# phase_reference.net
KiCad netlist of a schematic drawn in Altium Designer
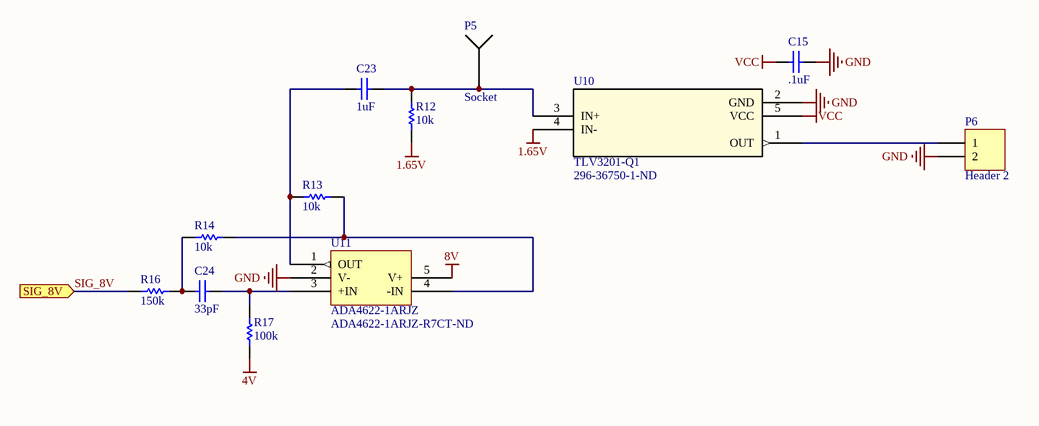
[diagram p0: phase_reference.SchDoc]

(export (version "E")
  (design (tool "Eeschema 10.0.6"))
  (components
    (comp (ref "C15")
      (value ".1uF")
      (footprint "0603")
      (description "Ceramic Capacitor (Surface Mount)")
      (fields (field (name "MANUFACTURER") "Generic Ceramic Chip Cap (TBD)") (field (name "Comment") "Cap"))
      (libsource (lib "maglib") (part "Cap"))
    )
    (comp (ref "C23")
      (value "1uF")
      (footprint "0603")
      (description "Ceramic Capacitor (Surface Mount)")
      (fields (field (name "MANUFACTURER") "Generic Ceramic Chip Cap (TBD)") (field (name "Comment") "Cap"))
      (libsource (lib "maglib") (part "Cap"))
    )
    (comp (ref "C24")
      (value "33pF")
      (footprint "0603")
      (description "Ceramic Capacitor (Surface Mount)")
      (fields (field (name "MANUFACTURER") "Generic Ceramic Chip Cap (TBD)") (field (name "Comment") "Cap"))
      (libsource (lib "maglib") (part "Cap"))
    )
    (comp (ref "P5") (value "Socket") (footprint "socket") (libsource (lib "maglib") (part "Socket")))
    (comp (ref "P6")
      (value "Header 2")
      (footprint "HDR1X2")
      (description "Header, 2-Pin")
      (fields (field (name "PUBLISHER") "Altium Limited"))
      (libsource (lib "Miscellaneous Connectors") (part "Header 2"))
    )
    (comp (ref "R12")
      (value "10k")
      (footprint "0603")
      (description "Chip Resistor (Surface Mount)")
      (fields (field (name "MANUFACTURER") "Generic Chip Res (TBD)") (field (name "Comment") "Res"))
      (libsource (lib "maglib") (part "Res"))
    )
    (comp (ref "R13")
      (value "10k")
      (footprint "0603")
      (description "Chip Resistor (Surface Mount)")
      (fields (field (name "MANUFACTURER") "Generic Chip Res (TBD)") (field (name "Comment") "Res"))
      (libsource (lib "maglib") (part "Res"))
    )
    (comp (ref "R14")
      (value "10k")
      (footprint "0603")
      (description "Chip Resistor (Surface Mount)")
      (fields (field (name "MANUFACTURER") "Generic Chip Res (TBD)") (field (name "Comment") "Res"))
      (libsource (lib "maglib") (part "Res"))
    )
    (comp (ref "R16")
      (value "150k")
      (footprint "0603")
      (description "Chip Resistor (Surface Mount)")
      (fields (field (name "MANUFACTURER") "Generic Chip Res (TBD)") (field (name "Comment") "Res"))
      (libsource (lib "maglib") (part "Res"))
    )
    (comp (ref "R17")
      (value "100k")
      (footprint "0603")
      (description "Chip Resistor (Surface Mount)")
      (fields (field (name "MANUFACTURER") "Generic Chip Res (TBD)") (field (name "Comment") "Res"))
      (libsource (lib "maglib") (part "Res"))
    )
    (comp (ref "U10")
      (value "TLV3201-Q1")
      (footprint "SOT95P280X145-5N")
      (description "40-ns, Micropower Comparator")
      (fields (field (name "SUPPLIER PART NUMBER 1") "296-36750-1-ND"))
      (libsource (lib "maglib") (part "TLV3201-Q1"))
    )
    (comp (ref "U11")
      (value "ADA4622-1ARJZ")
      (footprint "SOT95P280X145-5N")
      (description "30 V, 8 MHz, Low Bias Current,\r\nSingle-Supply, RRO, Precision Op Amps")
      (fields (field (name "SUPPLIER PART NUMBER 1") "ADA4622-1ARJZ-R7CT-ND"))
      (libsource (lib "maglib") (part "ADA4622-1ARJZ"))
    )
  )
  (nets
    (net (code "1") (name "/SIG_8V") (class "Default")
      (node (ref "R16") (pin "2") (pinfunction "2_2") (pintype "passive"))
    )
    (net (code "2") (name "1.65V") (class "Default")
      (node (ref "R12") (pin "1") (pinfunction "1_1") (pintype "passive"))
      (node (ref "U10") (pin "4") (pinfunction "IN-_4") (pintype "passive"))
    )
    (net (code "3") (name "4V") (class "Default")
      (node (ref "R17") (pin "1") (pinfunction "1_1") (pintype "passive"))
    )
    (net (code "4") (name "8V") (class "Default")
      (node (ref "U11") (pin "5") (pinfunction "V+_5") (pintype "power_in"))
    )
    (net (code "5") (name "GND") (class "Default")
      (node (ref "C15") (pin "2") (pinfunction "2_2") (pintype "passive"))
      (node (ref "P6") (pin "2") (pinfunction "2_2") (pintype "passive"))
      (node (ref "U10") (pin "2") (pinfunction "GND_2") (pintype "power_in"))
      (node (ref "U11") (pin "2") (pinfunction "V-_2") (pintype "power_in"))
    )
    (net (code "6") (name "Net-(C24-Pad2)") (class "Default")
      (node (ref "C24") (pin "2") (pinfunction "2_2") (pintype "passive"))
      (node (ref "R14") (pin "2") (pinfunction "2_2") (pintype "passive"))
      (node (ref "R16") (pin "1") (pinfunction "1_1") (pintype "passive"))
    )
    (net (code "7") (name "Net-(U10-IN+)") (class "Default")
      (node (ref "C23") (pin "1") (pinfunction "1_1") (pintype "passive"))
      (node (ref "P5") (pin "0") (pinfunction "0_0") (pintype "passive"))
      (node (ref "R12") (pin "2") (pinfunction "2_2") (pintype "passive"))
      (node (ref "U10") (pin "3") (pinfunction "IN+_3") (pintype "passive"))
    )
    (net (code "8") (name "Net-(U10-OUT)") (class "Default")
      (node (ref "P6") (pin "1") (pinfunction "1_1") (pintype "passive"))
      (node (ref "U10") (pin "1") (pinfunction "OUT_1") (pintype "output"))
    )
    (net (code "9") (name "Net-(U11-+IN)") (class "Default")
      (node (ref "C24") (pin "1") (pinfunction "1_1") (pintype "passive"))
      (node (ref "R17") (pin "2") (pinfunction "2_2") (pintype "passive"))
      (node (ref "U11") (pin "3") (pinfunction "+IN_3") (pintype "passive"))
    )
    (net (code "10") (name "Net-(U11--IN)") (class "Default")
      (node (ref "R13") (pin "1") (pinfunction "1_1") (pintype "passive"))
      (node (ref "R14") (pin "1") (pinfunction "1_1") (pintype "passive"))
      (node (ref "U11") (pin "4") (pinfunction "-IN_4") (pintype "passive"))
    )
    (net (code "11") (name "Net-(U11-OUT)") (class "Default")
      (node (ref "C23") (pin "2") (pinfunction "2_2") (pintype "passive"))
      (node (ref "R13") (pin "2") (pinfunction "2_2") (pintype "passive"))
      (node (ref "U11") (pin "1") (pinfunction "OUT_1") (pintype "output"))
    )
    (net (code "12") (name "VCC") (class "Default")
      (node (ref "C15") (pin "1") (pinfunction "1_1") (pintype "passive"))
      (node (ref "U10") (pin "5") (pinfunction "VCC_5") (pintype "power_in"))
    )
  )
)
